# SD.net
KiCad netlist of a schematic drawn in Altium Designer
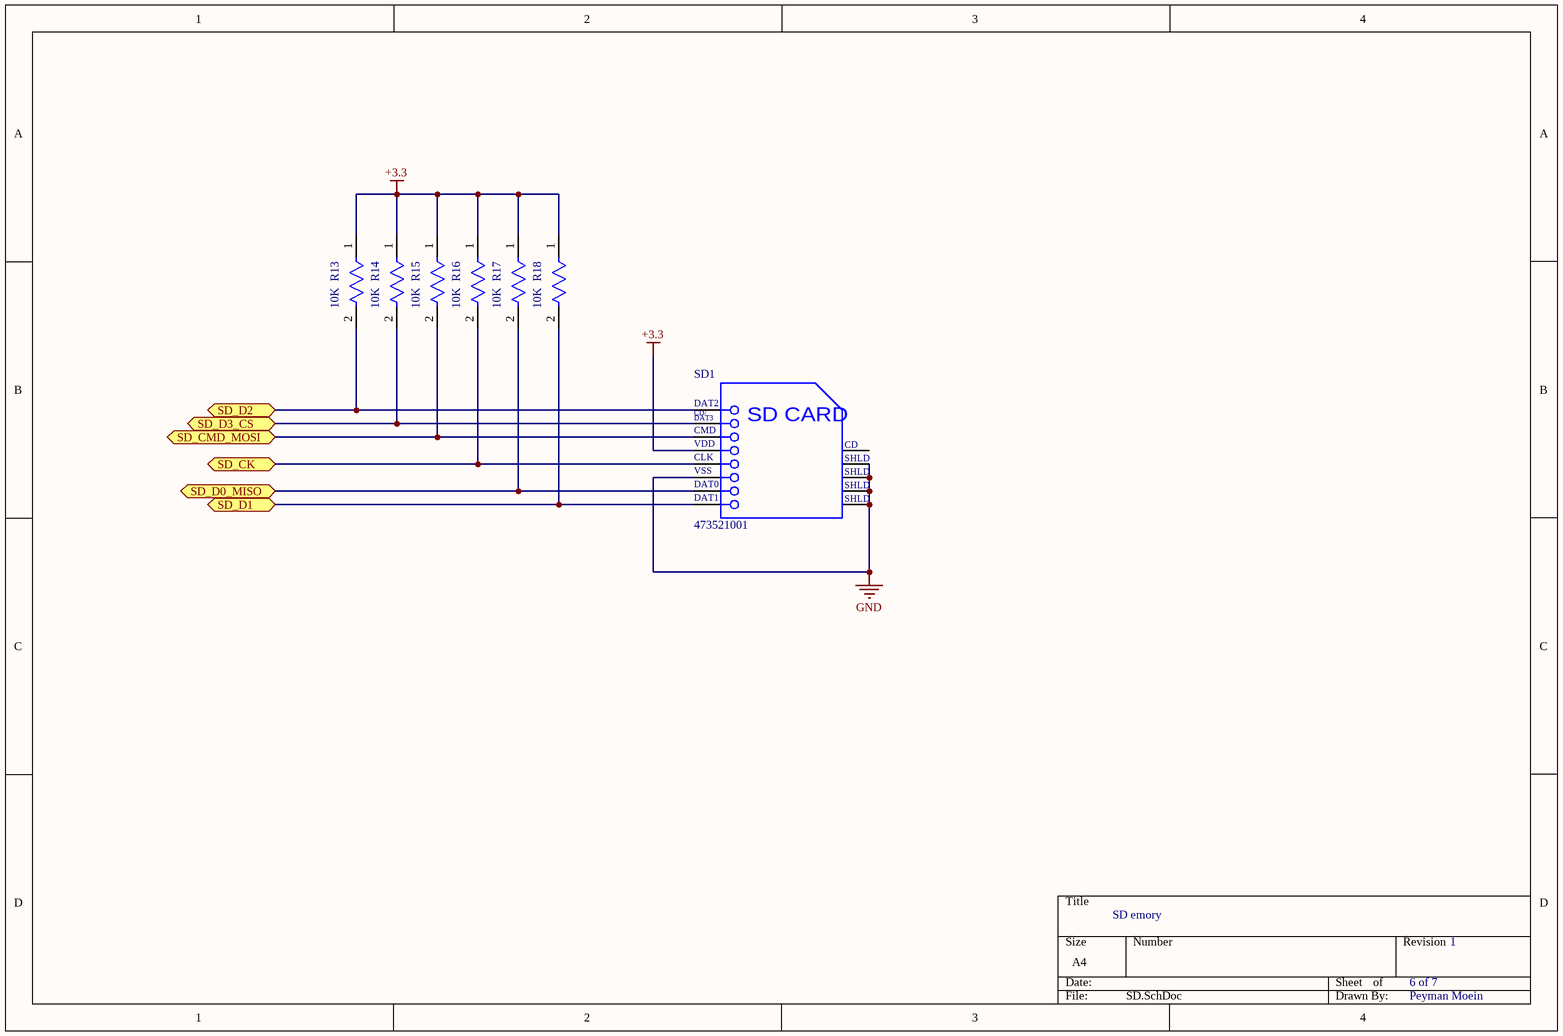
[diagram p0: SD.SchDoc]

(export (version "E")
  (design (tool "Eeschema 10.0.6"))
  (components
    (comp (ref "R13")
      (value "10K")
      (footprint "FP-CRCW0805-e3-MFG")
      (description "C478887")
      (fields (field (name "TOLERANCE") "1%"))
      (libsource (lib "Altium Content Vault") (part "1029c3af85768c4190bb7ad29bc67b5"))
    )
    (comp (ref "R14")
      (value "10K")
      (footprint "FP-CRCW0805-e3-MFG")
      (description "C478887")
      (fields (field (name "TOLERANCE") "1%"))
      (libsource (lib "Altium Content Vault") (part "1029c3af85768c4190bb7ad29bc67b5"))
    )
    (comp (ref "R15")
      (value "10K")
      (footprint "FP-CRCW0805-e3-MFG")
      (description "C478887")
      (fields (field (name "TOLERANCE") "1%"))
      (libsource (lib "Altium Content Vault") (part "1029c3af85768c4190bb7ad29bc67b5"))
    )
    (comp (ref "R16")
      (value "10K")
      (footprint "FP-CRCW0805-e3-MFG")
      (description "C478887")
      (fields (field (name "TOLERANCE") "1%"))
      (libsource (lib "Altium Content Vault") (part "1029c3af85768c4190bb7ad29bc67b5"))
    )
    (comp (ref "R17")
      (value "10K")
      (footprint "FP-CRCW0805-e3-MFG")
      (description "C478887")
      (fields (field (name "TOLERANCE") "1%"))
      (libsource (lib "Altium Content Vault") (part "1029c3af85768c4190bb7ad29bc67b5"))
    )
    (comp (ref "R18")
      (value "10K")
      (footprint "FP-CRCW0805-e3-MFG")
      (description "C478887")
      (fields (field (name "TOLERANCE") "1%"))
      (libsource (lib "Altium Content Vault") (part "1029c3af85768c4190bb7ad29bc67b5"))
    )
    (comp (ref "SD1")
      (value "473521001")
      (footprint "MOLX-473521001_V")
      (description "C293569")
      (fields (field (name "MANUFACTURER") "Molex"))
      (libsource (lib "Altium Content Vault") (part "CN-SD-8-1SW-4S"))
    )
  )
  (nets
    (net (code "1") (name "+3.3") (class "Default")
      (node (ref "R13") (pin "1") (pinfunction "1_1") (pintype "passive"))
      (node (ref "R14") (pin "1") (pinfunction "1_1") (pintype "passive"))
      (node (ref "R15") (pin "1") (pinfunction "1_1") (pintype "passive"))
      (node (ref "R16") (pin "1") (pinfunction "1_1") (pintype "passive"))
      (node (ref "R17") (pin "1") (pinfunction "1_1") (pintype "passive"))
      (node (ref "R18") (pin "1") (pinfunction "1_1") (pintype "passive"))
      (node (ref "SD1") (pin "4") (pinfunction "VDD_4") (pintype "passive"))
    )
    (net (code "2") (name "/SD_CK") (class "Default")
      (node (ref "R16") (pin "2") (pinfunction "2_2") (pintype "passive"))
      (node (ref "SD1") (pin "5") (pinfunction "CLK_5") (pintype "passive"))
    )
    (net (code "3") (name "/SD_CMD_MOSI") (class "Default")
      (node (ref "R15") (pin "2") (pinfunction "2_2") (pintype "passive"))
      (node (ref "SD1") (pin "3") (pinfunction "CMD_3") (pintype "passive"))
    )
    (net (code "4") (name "/SD_D0_MISO") (class "Default")
      (node (ref "R17") (pin "2") (pinfunction "2_2") (pintype "passive"))
      (node (ref "SD1") (pin "7") (pinfunction "DAT0_7") (pintype "passive"))
    )
    (net (code "5") (name "/SD_D1") (class "Default")
      (node (ref "R18") (pin "2") (pinfunction "2_2") (pintype "passive"))
      (node (ref "SD1") (pin "8") (pinfunction "DAT1_8") (pintype "passive"))
    )
    (net (code "6") (name "/SD_D2") (class "Default")
      (node (ref "R13") (pin "2") (pinfunction "2_2") (pintype "passive"))
      (node (ref "SD1") (pin "1") (pinfunction "DAT2_1") (pintype "passive"))
    )
    (net (code "7") (name "/SD_D3_CS") (class "Default")
      (node (ref "R14") (pin "2") (pinfunction "2_2") (pintype "passive"))
      (node (ref "SD1") (pin "2") (pinfunction "CD/DAT3_2") (pintype "passive"))
    )
    (net (code "8") (name "GND") (class "Default")
      (node (ref "SD1") (pin "10") (pinfunction "SHLD_10") (pintype "passive"))
      (node (ref "SD1") (pin "11") (pinfunction "SHLD_11") (pintype "passive"))
      (node (ref "SD1") (pin "12") (pinfunction "SHLD_12") (pintype "passive"))
      (node (ref "SD1") (pin "13") (pinfunction "SHLD_13") (pintype "passive"))
      (node (ref "SD1") (pin "6") (pinfunction "VSS_6") (pintype "passive"))
    )
    (net (code "9") (name "unconnected-(SD1-CD-Pad9)") (class "Default")
      (node (ref "SD1") (pin "9") (pinfunction "CD_9") (pintype "passive"))
    )
  )
)
